# goodfet42.net
KiCad netlist of a schematic drawn in EAGLE
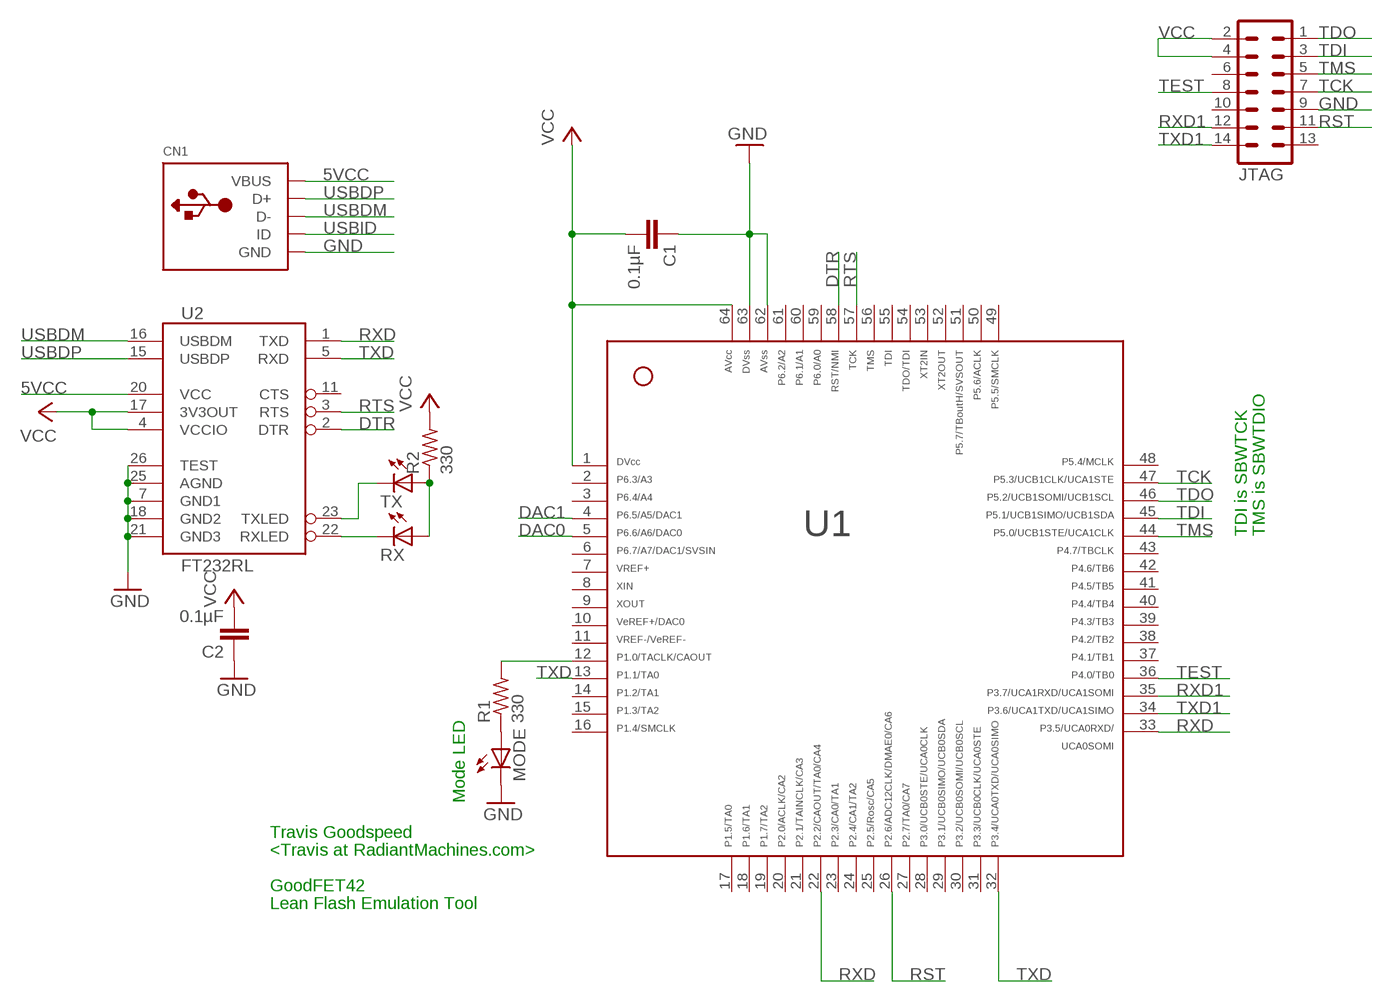
[diagram p0: schematic, sheet 1]

(export (version "E")
  (design (tool "Eeschema 10.0.6"))
  (components
    (comp (ref "C1")
      (value "0.1µF")
      (footprint "eagle-import:C0603")
      (libsource (lib "eagle-import") (part "C-EUC0603"))
    )
    (comp (ref "C2")
      (value "0.1µF")
      (footprint "eagle-import:C0603")
      (libsource (lib "eagle-import") (part "C-EUC0603"))
    )
    (comp (ref "CN1")
      (value "USBMINIB")
      (footprint "eagle-import:USB-MINIB")
      (libsource (lib "eagle-import") (part "USBMINIB"))
    )
    (comp (ref "JTAG")
      (value "MA07-2")
      (footprint "eagle-import:MA07-2")
      (libsource (lib "eagle-import") (part "MA07-2"))
    )
    (comp (ref "MODE")
      (value "LEDCHIP-LED0603")
      (footprint "eagle-import:CHIP-LED0603")
      (libsource (lib "eagle-import") (part "LEDCHIP-LED0603"))
    )
    (comp (ref "R1")
      (value "330")
      (footprint "eagle-import:R0603")
      (libsource (lib "eagle-import") (part "R-US_R0603"))
    )
    (comp (ref "R2")
      (value "330")
      (footprint "eagle-import:R0603")
      (libsource (lib "eagle-import") (part "R-US_R0603"))
    )
    (comp (ref "RX")
      (value "LEDCHIP-LED0603")
      (footprint "eagle-import:CHIP-LED0603")
      (libsource (lib "eagle-import") (part "LEDCHIP-LED0603"))
    )
    (comp (ref "TX")
      (value "LEDCHIP-LED0603")
      (footprint "eagle-import:CHIP-LED0603")
      (libsource (lib "eagle-import") (part "LEDCHIP-LED0603"))
    )
    (comp (ref "U1")
      (value "MSP430F2618TPM")
      (footprint "eagle-import:PM_PAG64")
      (libsource (lib "eagle-import") (part "F261X---PM64"))
    )
    (comp (ref "U2")
      (value "FT232RL")
      (footprint "eagle-import:SSOP28DB")
      (libsource (lib "eagle-import") (part "FT232RL-BASICSSOP"))
    )
  )
  (nets
    (net (code "1") (name "/5VCC") (class "Default")
      (node (ref "CN1") (pin "VBUS") (pinfunction "VBUS_VBUS") (pintype "power_in"))
      (node (ref "U2") (pin "20") (pinfunction "VCC_20") (pintype "power_in"))
    )
    (net (code "2") (name "/DAC0") (class "Default")
      (node (ref "U1") (pin "5") (pinfunction "5_5") (pintype "bidirectional"))
    )
    (net (code "3") (name "/DAC1") (class "Default")
      (node (ref "U1") (pin "4") (pinfunction "4_4") (pintype "bidirectional"))
    )
    (net (code "4") (name "/DTR") (class "Default")
      (node (ref "U1") (pin "58") (pinfunction "58_58") (pintype "input"))
      (node (ref "U2") (pin "2") (pinfunction "DTR_2") (pintype "bidirectional"))
    )
    (net (code "5") (name "/RST") (class "Default")
      (node (ref "JTAG") (pin "11") (pinfunction "11_11") (pintype "passive"))
      (node (ref "U1") (pin "26") (pinfunction "26_26") (pintype "bidirectional"))
    )
    (net (code "6") (name "/RTS") (class "Default")
      (node (ref "U1") (pin "57") (pinfunction "57_57") (pintype "input"))
      (node (ref "U2") (pin "3") (pinfunction "RTS_3") (pintype "bidirectional"))
    )
    (net (code "7") (name "/RXD") (class "Default")
      (node (ref "U1") (pin "22") (pinfunction "22_22") (pintype "bidirectional"))
      (node (ref "U1") (pin "33") (pinfunction "33_33") (pintype "bidirectional"))
      (node (ref "U2") (pin "1") (pinfunction "TXD_1") (pintype "output"))
    )
    (net (code "8") (name "/RXD1") (class "Default")
      (node (ref "JTAG") (pin "12") (pinfunction "12_12") (pintype "passive"))
      (node (ref "U1") (pin "35") (pinfunction "35_35") (pintype "bidirectional"))
    )
    (net (code "9") (name "/TCK") (class "Default")
      (node (ref "JTAG") (pin "7") (pinfunction "7_7") (pintype "passive"))
      (node (ref "U1") (pin "47") (pinfunction "47_47") (pintype "bidirectional"))
    )
    (net (code "10") (name "/TDI") (class "Default")
      (node (ref "JTAG") (pin "3") (pinfunction "3_3") (pintype "passive"))
      (node (ref "U1") (pin "45") (pinfunction "45_45") (pintype "bidirectional"))
    )
    (net (code "11") (name "/TDO") (class "Default")
      (node (ref "JTAG") (pin "1") (pinfunction "1_1") (pintype "passive"))
      (node (ref "U1") (pin "46") (pinfunction "46_46") (pintype "bidirectional"))
    )
    (net (code "12") (name "/TEST") (class "Default")
      (node (ref "JTAG") (pin "8") (pinfunction "8_8") (pintype "passive"))
      (node (ref "U1") (pin "36") (pinfunction "36_36") (pintype "output"))
    )
    (net (code "13") (name "/TMS") (class "Default")
      (node (ref "JTAG") (pin "5") (pinfunction "5_5") (pintype "passive"))
      (node (ref "U1") (pin "44") (pinfunction "44_44") (pintype "bidirectional"))
    )
    (net (code "14") (name "/TXD") (class "Default")
      (node (ref "U1") (pin "13") (pinfunction "13_13") (pintype "bidirectional"))
      (node (ref "U1") (pin "32") (pinfunction "32_32") (pintype "bidirectional"))
      (node (ref "U2") (pin "5") (pinfunction "RXD_5") (pintype "input"))
    )
    (net (code "15") (name "/TXD1") (class "Default")
      (node (ref "JTAG") (pin "14") (pinfunction "14_14") (pintype "passive"))
      (node (ref "U1") (pin "34") (pinfunction "34_34") (pintype "bidirectional"))
    )
    (net (code "16") (name "/USBDM") (class "Default")
      (node (ref "CN1") (pin "D-") (pinfunction "D-_D-") (pintype "bidirectional"))
      (node (ref "U2") (pin "16") (pinfunction "USBDM_16") (pintype "bidirectional"))
    )
    (net (code "17") (name "/USBDP") (class "Default")
      (node (ref "CN1") (pin "D+") (pinfunction "D+_D+") (pintype "bidirectional"))
      (node (ref "U2") (pin "15") (pinfunction "USBDP_15") (pintype "bidirectional"))
    )
    (net (code "18") (name "/USBID") (class "Default")
      (node (ref "CN1") (pin "ID") (pinfunction "ID_ID") (pintype "bidirectional"))
    )
    (net (code "19") (name "GND") (class "Default")
      (node (ref "C1") (pin "1") (pinfunction "1_1") (pintype "passive"))
      (node (ref "C2") (pin "1") (pinfunction "1_1") (pintype "passive"))
      (node (ref "CN1") (pin "GND") (pinfunction "GND_GND") (pintype "power_in"))
      (node (ref "JTAG") (pin "9") (pinfunction "9_9") (pintype "passive"))
      (node (ref "MODE") (pin "C") (pinfunction "C_C") (pintype "passive"))
      (node (ref "U1") (pin "62") (pinfunction "62_62") (pintype "power_in"))
      (node (ref "U1") (pin "63") (pinfunction "63_63") (pintype "power_in"))
      (node (ref "U2") (pin "18") (pinfunction "GND2_18") (pintype "power_in"))
      (node (ref "U2") (pin "21") (pinfunction "GND3_21") (pintype "power_in"))
      (node (ref "U2") (pin "25") (pinfunction "AGND_25") (pintype "power_in"))
      (node (ref "U2") (pin "26") (pinfunction "TEST_26") (pintype "input"))
      (node (ref "U2") (pin "7") (pinfunction "GND1_7") (pintype "power_in"))
    )
    (net (code "20") (name "Net-(MODE-PadA)") (class "Default")
      (node (ref "MODE") (pin "A") (pinfunction "A_A") (pintype "passive"))
      (node (ref "R1") (pin "1") (pinfunction "1_1") (pintype "passive"))
    )
    (net (code "21") (name "Net-(R1-Pad2)") (class "Default")
      (node (ref "R1") (pin "2") (pinfunction "2_2") (pintype "passive"))
      (node (ref "U1") (pin "12") (pinfunction "12_12") (pintype "bidirectional"))
    )
    (net (code "22") (name "Net-(R2-Pad1)") (class "Default")
      (node (ref "R2") (pin "1") (pinfunction "1_1") (pintype "passive"))
      (node (ref "RX") (pin "A") (pinfunction "A_A") (pintype "passive"))
      (node (ref "TX") (pin "A") (pinfunction "A_A") (pintype "passive"))
    )
    (net (code "23") (name "Net-(U2-RXLED)") (class "Default")
      (node (ref "RX") (pin "C") (pinfunction "C_C") (pintype "passive"))
      (node (ref "U2") (pin "22") (pinfunction "RXLED_22") (pintype "bidirectional"))
    )
    (net (code "24") (name "Net-(U2-TXLED)") (class "Default")
      (node (ref "TX") (pin "C") (pinfunction "C_C") (pintype "passive"))
      (node (ref "U2") (pin "23") (pinfunction "TXLED_23") (pintype "bidirectional"))
    )
    (net (code "25") (name "VCC") (class "Default")
      (node (ref "C1") (pin "2") (pinfunction "2_2") (pintype "passive"))
      (node (ref "C2") (pin "2") (pinfunction "2_2") (pintype "passive"))
      (node (ref "JTAG") (pin "2") (pinfunction "2_2") (pintype "passive"))
      (node (ref "JTAG") (pin "4") (pinfunction "4_4") (pintype "passive"))
      (node (ref "R2") (pin "2") (pinfunction "2_2") (pintype "passive"))
      (node (ref "U1") (pin "1") (pinfunction "1_1") (pintype "power_in"))
      (node (ref "U1") (pin "64") (pinfunction "64_64") (pintype "power_in"))
      (node (ref "U2") (pin "17") (pinfunction "3V3OUT_17") (pintype "output"))
      (node (ref "U2") (pin "4") (pinfunction "VCCIO_4") (pintype "power_in"))
    )
    (net (code "26") (name "unconnected-(JTAG-Pad6)") (class "Default")
      (node (ref "JTAG") (pin "6") (pinfunction "6_6") (pintype "passive"))
    )
    (net (code "27") (name "unconnected-(JTAG-Pad10)") (class "Default")
      (node (ref "JTAG") (pin "10") (pinfunction "10_10") (pintype "passive"))
    )
    (net (code "28") (name "unconnected-(JTAG-Pad13)") (class "Default")
      (node (ref "JTAG") (pin "13") (pinfunction "13_13") (pintype "passive"))
    )
    (net (code "29") (name "unconnected-(U1-Pad2)") (class "Default")
      (node (ref "U1") (pin "2") (pinfunction "2_2") (pintype "bidirectional"))
    )
    (net (code "30") (name "unconnected-(U1-Pad3)") (class "Default")
      (node (ref "U1") (pin "3") (pinfunction "3_3") (pintype "bidirectional"))
    )
    (net (code "31") (name "unconnected-(U1-Pad6)") (class "Default")
      (node (ref "U1") (pin "6") (pinfunction "6_6") (pintype "bidirectional"))
    )
    (net (code "32") (name "unconnected-(U1-Pad7)") (class "Default")
      (node (ref "U1") (pin "7") (pinfunction "7_7") (pintype "output"))
    )
    (net (code "33") (name "unconnected-(U1-Pad8)") (class "Default")
      (node (ref "U1") (pin "8") (pinfunction "8_8") (pintype "input"))
    )
    (net (code "34") (name "unconnected-(U1-Pad9)") (class "Default")
      (node (ref "U1") (pin "9") (pinfunction "9_9") (pintype "output"))
    )
    (net (code "35") (name "unconnected-(U1-Pad10)") (class "Default")
      (node (ref "U1") (pin "10") (pinfunction "10_10") (pintype "bidirectional"))
    )
    (net (code "36") (name "unconnected-(U1-Pad11)") (class "Default")
      (node (ref "U1") (pin "11") (pinfunction "11_11") (pintype "bidirectional"))
    )
    (net (code "37") (name "unconnected-(U1-Pad14)") (class "Default")
      (node (ref "U1") (pin "14") (pinfunction "14_14") (pintype "bidirectional"))
    )
    (net (code "38") (name "unconnected-(U1-Pad15)") (class "Default")
      (node (ref "U1") (pin "15") (pinfunction "15_15") (pintype "bidirectional"))
    )
    (net (code "39") (name "unconnected-(U1-Pad16)") (class "Default")
      (node (ref "U1") (pin "16") (pinfunction "16_16") (pintype "bidirectional"))
    )
    (net (code "40") (name "unconnected-(U1-Pad17)") (class "Default")
      (node (ref "U1") (pin "17") (pinfunction "17_17") (pintype "bidirectional"))
    )
    (net (code "41") (name "unconnected-(U1-Pad18)") (class "Default")
      (node (ref "U1") (pin "18") (pinfunction "18_18") (pintype "bidirectional"))
    )
    (net (code "42") (name "unconnected-(U1-Pad19)") (class "Default")
      (node (ref "U1") (pin "19") (pinfunction "19_19") (pintype "bidirectional"))
    )
    (net (code "43") (name "unconnected-(U1-Pad20)") (class "Default")
      (node (ref "U1") (pin "20") (pinfunction "20_20") (pintype "bidirectional"))
    )
    (net (code "44") (name "unconnected-(U1-Pad21)") (class "Default")
      (node (ref "U1") (pin "21") (pinfunction "21_21") (pintype "bidirectional"))
    )
    (net (code "45") (name "unconnected-(U1-Pad23)") (class "Default")
      (node (ref "U1") (pin "23") (pinfunction "23_23") (pintype "bidirectional"))
    )
    (net (code "46") (name "unconnected-(U1-Pad24)") (class "Default")
      (node (ref "U1") (pin "24") (pinfunction "24_24") (pintype "bidirectional"))
    )
    (net (code "47") (name "unconnected-(U1-Pad25)") (class "Default")
      (node (ref "U1") (pin "25") (pinfunction "25_25") (pintype "bidirectional"))
    )
    (net (code "48") (name "unconnected-(U1-Pad27)") (class "Default")
      (node (ref "U1") (pin "27") (pinfunction "27_27") (pintype "bidirectional"))
    )
    (net (code "49") (name "unconnected-(U1-Pad28)") (class "Default")
      (node (ref "U1") (pin "28") (pinfunction "28_28") (pintype "bidirectional"))
    )
    (net (code "50") (name "unconnected-(U1-Pad29)") (class "Default")
      (node (ref "U1") (pin "29") (pinfunction "29_29") (pintype "bidirectional"))
    )
    (net (code "51") (name "unconnected-(U1-Pad30)") (class "Default")
      (node (ref "U1") (pin "30") (pinfunction "30_30") (pintype "bidirectional"))
    )
    (net (code "52") (name "unconnected-(U1-Pad31)") (class "Default")
      (node (ref "U1") (pin "31") (pinfunction "31_31") (pintype "bidirectional"))
    )
    (net (code "53") (name "unconnected-(U1-Pad37)") (class "Default")
      (node (ref "U1") (pin "37") (pinfunction "37_37") (pintype "bidirectional"))
    )
    (net (code "54") (name "unconnected-(U1-Pad38)") (class "Default")
      (node (ref "U1") (pin "38") (pinfunction "38_38") (pintype "bidirectional"))
    )
    (net (code "55") (name "unconnected-(U1-Pad39)") (class "Default")
      (node (ref "U1") (pin "39") (pinfunction "39_39") (pintype "bidirectional"))
    )
    (net (code "56") (name "unconnected-(U1-Pad40)") (class "Default")
      (node (ref "U1") (pin "40") (pinfunction "40_40") (pintype "input"))
    )
    (net (code "57") (name "unconnected-(U1-Pad41)") (class "Default")
      (node (ref "U1") (pin "41") (pinfunction "41_41") (pintype "bidirectional"))
    )
    (net (code "58") (name "unconnected-(U1-Pad42)") (class "Default")
      (node (ref "U1") (pin "42") (pinfunction "42_42") (pintype "bidirectional"))
    )
    (net (code "59") (name "unconnected-(U1-Pad43)") (class "Default")
      (node (ref "U1") (pin "43") (pinfunction "43_43") (pintype "bidirectional"))
    )
    (net (code "60") (name "unconnected-(U1-Pad48)") (class "Default")
      (node (ref "U1") (pin "48") (pinfunction "48_48") (pintype "bidirectional"))
    )
    (net (code "61") (name "unconnected-(U1-Pad49)") (class "Default")
      (node (ref "U1") (pin "49") (pinfunction "49_49") (pintype "bidirectional"))
    )
    (net (code "62") (name "unconnected-(U1-Pad50)") (class "Default")
      (node (ref "U1") (pin "50") (pinfunction "50_50") (pintype "bidirectional"))
    )
    (net (code "63") (name "unconnected-(U1-Pad51)") (class "Default")
      (node (ref "U1") (pin "51") (pinfunction "51_51") (pintype "bidirectional"))
    )
    (net (code "64") (name "unconnected-(U1-Pad52)") (class "Default")
      (node (ref "U1") (pin "52") (pinfunction "52_52") (pintype "output"))
    )
    (net (code "65") (name "unconnected-(U1-Pad53)") (class "Default")
      (node (ref "U1") (pin "53") (pinfunction "53_53") (pintype "input"))
    )
    (net (code "66") (name "unconnected-(U1-Pad54)") (class "Default")
      (node (ref "U1") (pin "54") (pinfunction "54_54") (pintype "bidirectional"))
    )
    (net (code "67") (name "unconnected-(U1-Pad55)") (class "Default")
      (node (ref "U1") (pin "55") (pinfunction "55_55") (pintype "input"))
    )
    (net (code "68") (name "unconnected-(U1-Pad56)") (class "Default")
      (node (ref "U1") (pin "56") (pinfunction "56_56") (pintype "input"))
    )
    (net (code "69") (name "unconnected-(U1-Pad59)") (class "Default")
      (node (ref "U1") (pin "59") (pinfunction "59_59") (pintype "bidirectional"))
    )
    (net (code "70") (name "unconnected-(U1-Pad60)") (class "Default")
      (node (ref "U1") (pin "60") (pinfunction "60_60") (pintype "bidirectional"))
    )
    (net (code "71") (name "unconnected-(U1-Pad61)") (class "Default")
      (node (ref "U1") (pin "61") (pinfunction "61_61") (pintype "bidirectional"))
    )
    (net (code "72") (name "unconnected-(U2-CTS-Pad11)") (class "Default")
      (node (ref "U2") (pin "11") (pinfunction "CTS_11") (pintype "bidirectional"))
    )
  )
)
